# Battery-Indicator.net
KiCad netlist of a schematic drawn in Altium Designer
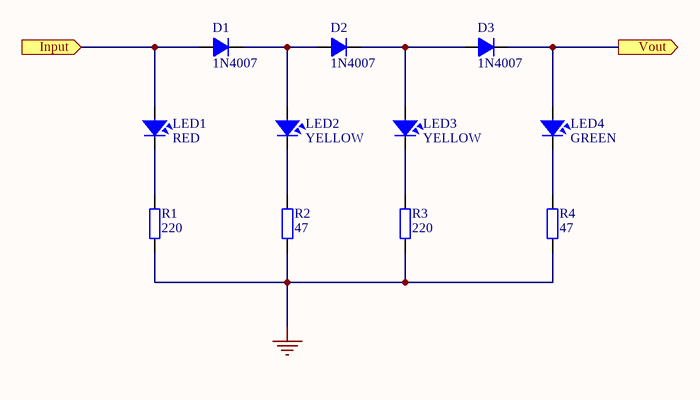
[diagram p0: Battery-Indicator.SchDoc]

(export (version "E")
  (design (tool "Eeschema 10.0.6"))
  (components
    (comp (ref "D1")
      (value "1N4007")
      (footprint "D1A")
      (description "Diode 1A")
      (libsource (lib "My Library.~(1)") (part "D1A"))
    )
    (comp (ref "D2")
      (value "1N4007")
      (footprint "D1A")
      (description "Diode 1A")
      (libsource (lib "My Library.~(1)") (part "D1A"))
    )
    (comp (ref "D3")
      (value "1N4007")
      (footprint "D1A")
      (description "Diode 1A")
      (libsource (lib "My Library.~(1)") (part "D1A"))
    )
    (comp (ref "LED1")
      (value "RED")
      (footprint "LED-3")
      (description "LED Single colour Green and Red")
      (libsource (lib "My Library.~(1)") (part "LED"))
    )
    (comp (ref "LED2")
      (value "YELLOW")
      (footprint "LED-3")
      (description "LED Single colour Green and Red")
      (libsource (lib "My Library.~(1)") (part "LED"))
    )
    (comp (ref "LED3")
      (value "YELLOW")
      (footprint "LED-3")
      (description "LED Single colour Green and Red")
      (libsource (lib "My Library.~(1)") (part "LED"))
    )
    (comp (ref "LED4")
      (value "GREEN")
      (footprint "LED-3")
      (description "LED Single colour Green and Red")
      (libsource (lib "My Library.~(1)") (part "LED"))
    )
    (comp (ref "R1")
      (value "220")
      (footprint "RES_0805")
      (description "Resistor SMD 0805")
      (libsource (lib "Schematic-Lib-PhilsLab") (part "RES_0805"))
    )
    (comp (ref "R2")
      (value "47")
      (footprint "RES_0805")
      (description "Resistor SMD 0805")
      (libsource (lib "Schematic-Lib-PhilsLab") (part "RES_0805"))
    )
    (comp (ref "R3")
      (value "220")
      (footprint "RES_0805")
      (description "Resistor SMD 0805")
      (libsource (lib "Schematic-Lib-PhilsLab") (part "RES_0805"))
    )
    (comp (ref "R4")
      (value "47")
      (footprint "RES_0805")
      (description "Resistor SMD 0805")
      (libsource (lib "Schematic-Lib-PhilsLab") (part "RES_0805"))
    )
  )
  (nets
    (net (code "1") (name "/Input") (class "Default")
      (node (ref "D1") (pin "1") (pinfunction "A_1") (pintype "passive"))
      (node (ref "LED1") (pin "1") (pinfunction "1_1") (pintype "passive"))
    )
    (net (code "2") (name "/Vout") (class "Default")
      (node (ref "D3") (pin "2") (pinfunction "K_2") (pintype "passive"))
      (node (ref "LED4") (pin "1") (pinfunction "1_1") (pintype "passive"))
    )
    (net (code "3") (name "GND") (class "Default")
      (node (ref "R1") (pin "1") (pinfunction "1_1") (pintype "passive"))
      (node (ref "R2") (pin "1") (pinfunction "1_1") (pintype "passive"))
      (node (ref "R3") (pin "1") (pinfunction "1_1") (pintype "passive"))
      (node (ref "R4") (pin "1") (pinfunction "1_1") (pintype "passive"))
    )
    (net (code "4") (name "Net-(D1-K)") (class "Default")
      (node (ref "D1") (pin "2") (pinfunction "K_2") (pintype "passive"))
      (node (ref "D2") (pin "1") (pinfunction "A_1") (pintype "passive"))
      (node (ref "LED2") (pin "1") (pinfunction "1_1") (pintype "passive"))
    )
    (net (code "5") (name "Net-(D2-K)") (class "Default")
      (node (ref "D2") (pin "2") (pinfunction "K_2") (pintype "passive"))
      (node (ref "D3") (pin "1") (pinfunction "A_1") (pintype "passive"))
      (node (ref "LED3") (pin "1") (pinfunction "1_1") (pintype "passive"))
    )
    (net (code "6") (name "Net-(LED1-Pad2)") (class "Default")
      (node (ref "LED1") (pin "2") (pinfunction "2_2") (pintype "passive"))
      (node (ref "R1") (pin "2") (pinfunction "2_2") (pintype "passive"))
    )
    (net (code "7") (name "Net-(LED2-Pad2)") (class "Default")
      (node (ref "LED2") (pin "2") (pinfunction "2_2") (pintype "passive"))
      (node (ref "R2") (pin "2") (pinfunction "2_2") (pintype "passive"))
    )
    (net (code "8") (name "Net-(LED3-Pad2)") (class "Default")
      (node (ref "LED3") (pin "2") (pinfunction "2_2") (pintype "passive"))
      (node (ref "R3") (pin "2") (pinfunction "2_2") (pintype "passive"))
    )
    (net (code "9") (name "Net-(LED4-Pad2)") (class "Default")
      (node (ref "LED4") (pin "2") (pinfunction "2_2") (pintype "passive"))
      (node (ref "R4") (pin "2") (pinfunction "2_2") (pintype "passive"))
    )
  )
)
